# 11-_IMU.net
KiCad netlist of a schematic drawn in Altium Designer
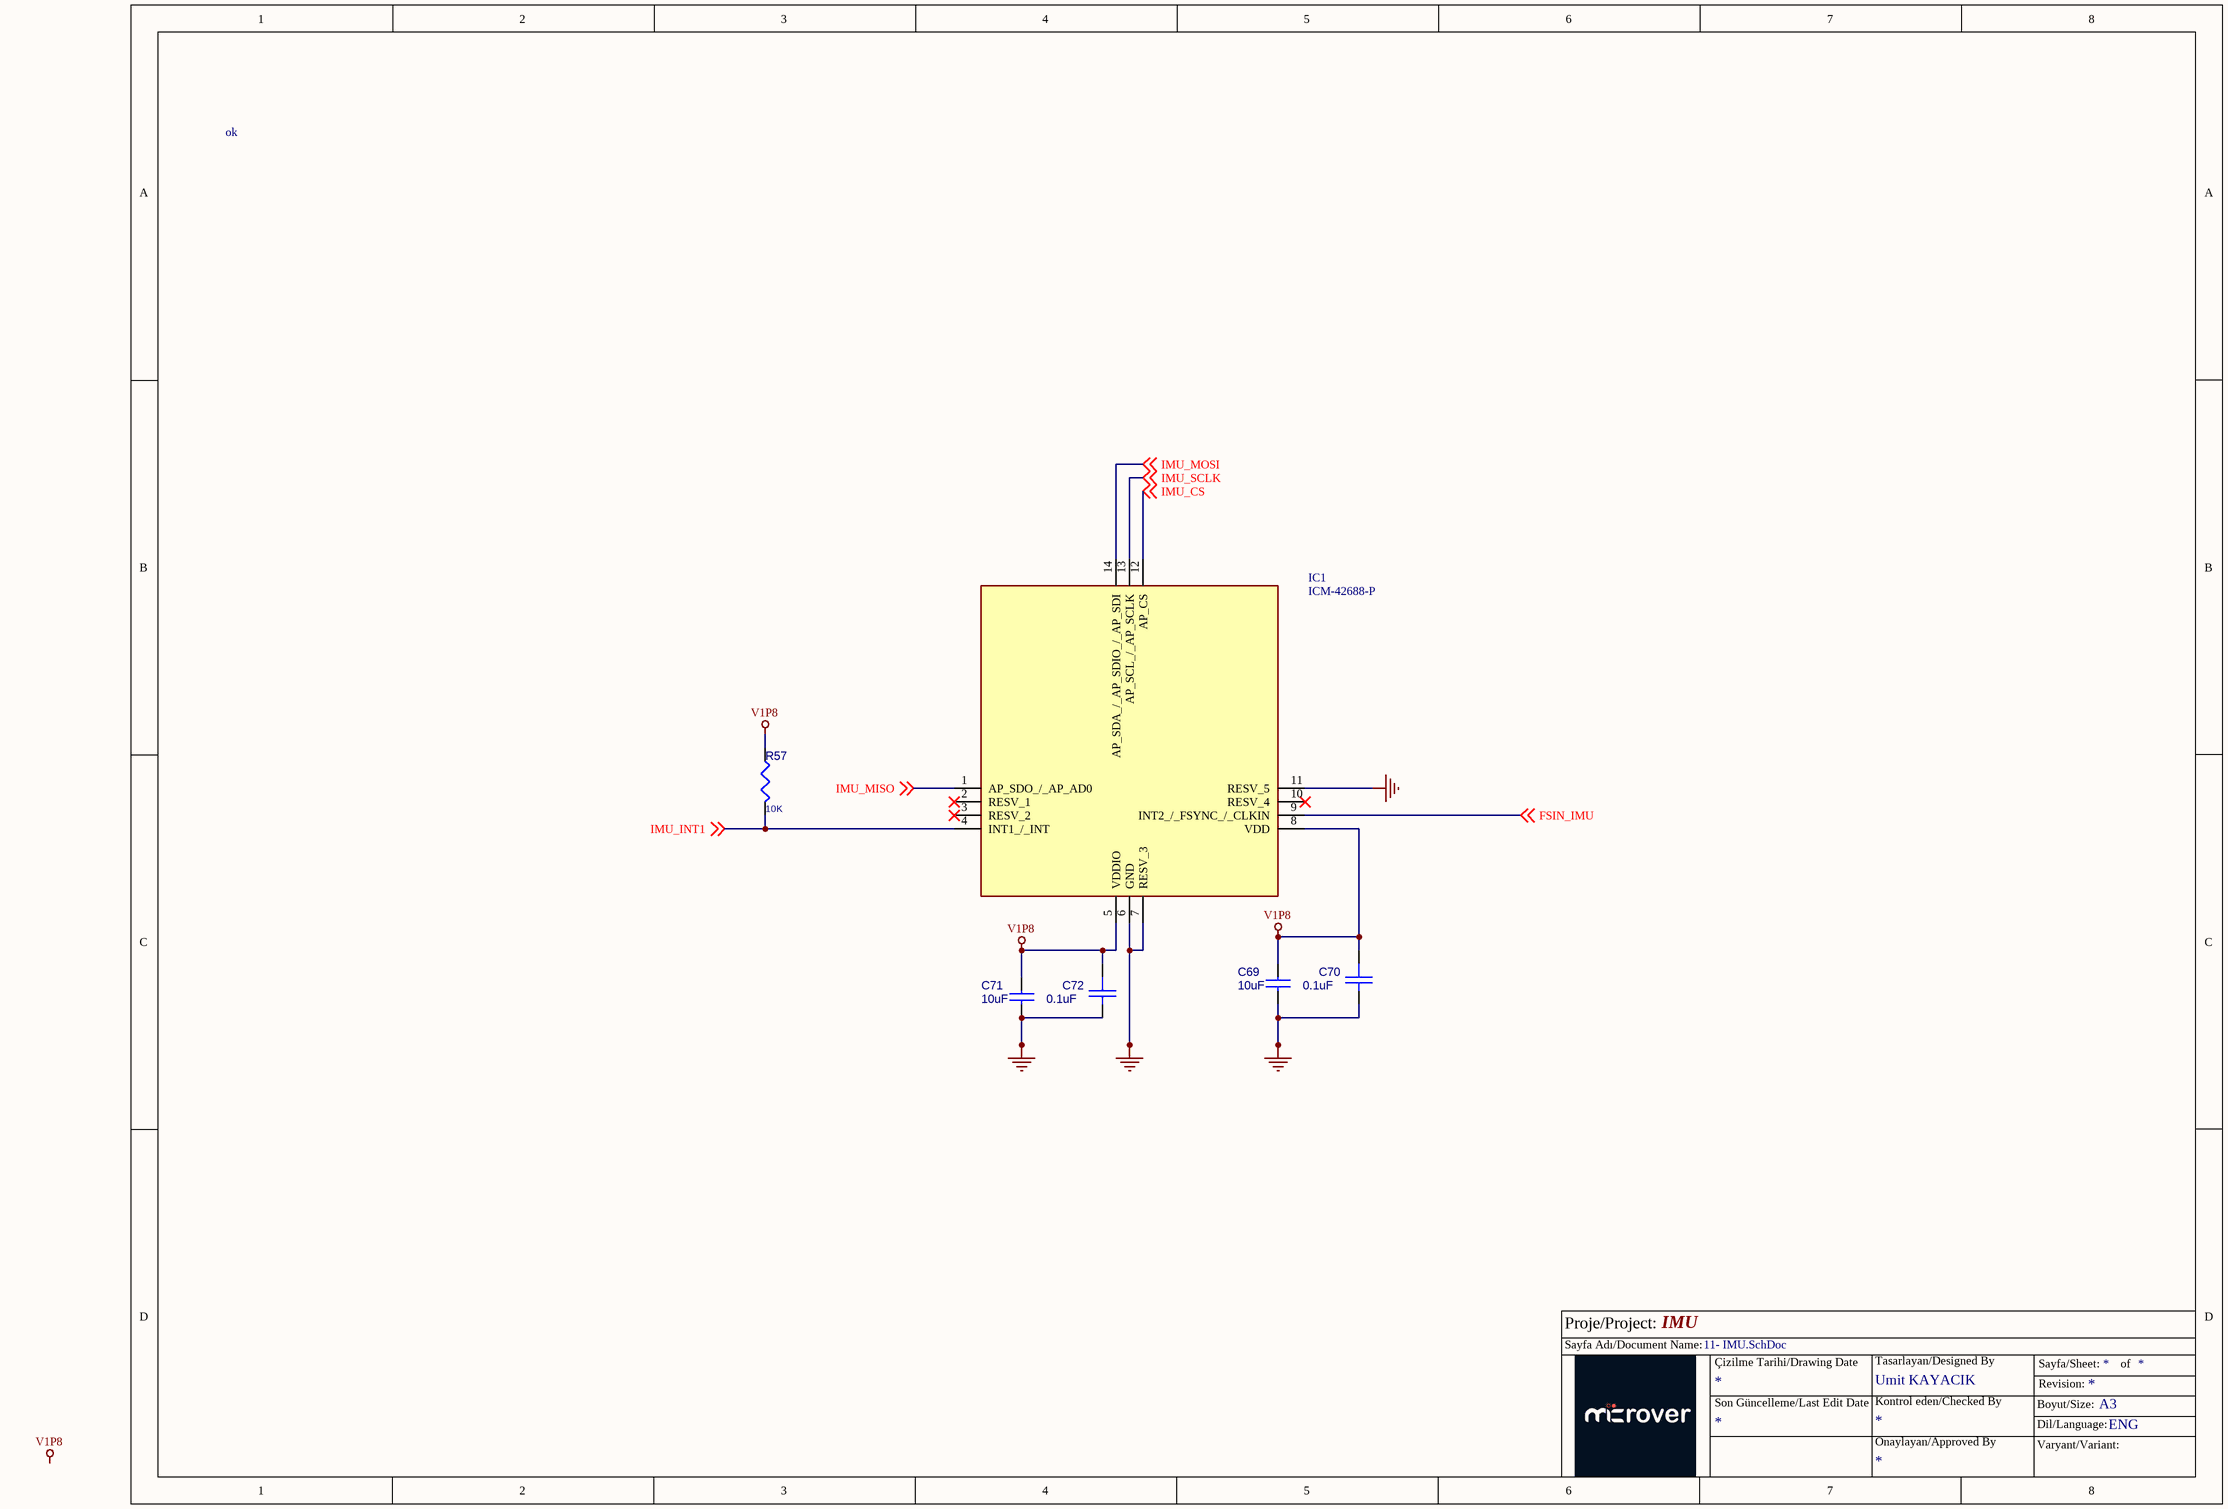
[diagram p0: 11- IMU.SchDoc]

(export (version "E")
  (design (tool "Eeschema 10.0.6"))
  (components
    (comp (ref "C69")
      (value "10uF")
      (footprint "C0603")
      (description "CAP CER 10UF 10V 20% X6S 0603")
      (fields (field (name "MFG") "Samsung") (field (name "MAN. PART #") "CL10X106MP8NRNC"))
      (libsource (lib "*") (part "CAP NP"))
    )
    (comp (ref "C70")
      (value "0.1uF")
      (footprint "C0201")
      (description "CAP CER 0.1UF 25V 10% X5R 0201")
      (fields
        (field (name "MANUFACTURER") "Murata")
        (field (name "MANUFACTURER PART NUMBER") "GRM033R61E104KE14J")
      )
      (libsource (lib "*") (part "CAP_SMT_0805"))
    )
    (comp (ref "C71")
      (value "10uF")
      (footprint "C0603")
      (description "CAP CER 10UF 10V 20% X6S 0603")
      (fields (field (name "MFG") "Samsung") (field (name "MAN. PART #") "CL10X106MP8NRNC"))
      (libsource (lib "*") (part "CAP NP"))
    )
    (comp (ref "C72")
      (value "0.1uF")
      (footprint "C0201")
      (description "CAP CER 0.1UF 25V 10% X5R 0201")
      (fields
        (field (name "MANUFACTURER") "Murata")
        (field (name "MANUFACTURER PART NUMBER") "GRM033R61E104KE14J")
      )
      (libsource (lib "*") (part "CAP_SMT_0805"))
    )
    (comp (ref "IC1")
      (value "ICM-42688-P")
      (footprint "IIM42352")
      (description "Integrated Circuit")
      (fields (field (name "MOUSER PART NUMBER") "410-ICM-42688-P"))
      (libsource (lib "Chronos") (part "ICM-42688-P"))
    )
    (comp (ref "R57")
      (value "10K")
      (footprint "R0402")
      (description "RES 10K OHM 1/10W 5% 0603")
      (fields
        (field (name "MFG") "Stackpole Electronics Inc")
        (field (name "MANUFACTURER PART NUMBER") "RMCF0603JT10K0")
      )
      (libsource (lib "*") (part "RES_10K_1W16_0402_5P"))
    )
  )
  (nets
    (net (code "1") (name "FSIN_IMU") (class "Default")
      (node (ref "IC1") (pin "9") (pinfunction "INT2_/_FSYNC_/_CLKIN_9") (pintype "passive"))
    )
    (net (code "2") (name "GND") (class "Default")
      (node (ref "C69") (pin "2") (pinfunction "2_2") (pintype "passive"))
      (node (ref "C70") (pin "2") (pinfunction "2_2") (pintype "passive"))
      (node (ref "C71") (pin "2") (pinfunction "2_2") (pintype "passive"))
      (node (ref "C72") (pin "2") (pinfunction "2_2") (pintype "passive"))
      (node (ref "IC1") (pin "11") (pinfunction "RESV_5_11") (pintype "passive"))
      (node (ref "IC1") (pin "6") (pinfunction "GND_6") (pintype "passive"))
      (node (ref "IC1") (pin "7") (pinfunction "RESV_3_7") (pintype "passive"))
    )
    (net (code "3") (name "IMU_CS") (class "Default")
      (node (ref "IC1") (pin "12") (pinfunction "AP_CS_12") (pintype "passive"))
    )
    (net (code "4") (name "IMU_INT1") (class "Default")
      (node (ref "IC1") (pin "4") (pinfunction "INT1_/_INT_4") (pintype "passive"))
      (node (ref "R57") (pin "2") (pinfunction "2_2") (pintype "passive"))
    )
    (net (code "5") (name "IMU_MISO") (class "Default")
      (node (ref "IC1") (pin "1") (pinfunction "AP_SDO_/_AP_AD0_1") (pintype "passive"))
    )
    (net (code "6") (name "IMU_MOSI") (class "Default")
      (node (ref "IC1") (pin "14") (pinfunction "AP_SDA_/_AP_SDIO_/_AP_SDI_14") (pintype "passive"))
    )
    (net (code "7") (name "IMU_SCLK") (class "Default")
      (node (ref "IC1") (pin "13") (pinfunction "AP_SCL_/_AP_SCLK_13") (pintype "passive"))
    )
    (net (code "8") (name "V1P8") (class "Default")
      (node (ref "C69") (pin "1") (pinfunction "1_1") (pintype "passive"))
      (node (ref "C70") (pin "1") (pinfunction "1_1") (pintype "passive"))
      (node (ref "C71") (pin "1") (pinfunction "1_1") (pintype "passive"))
      (node (ref "C72") (pin "1") (pinfunction "1_1") (pintype "passive"))
      (node (ref "IC1") (pin "5") (pinfunction "VDDIO_5") (pintype "passive"))
      (node (ref "IC1") (pin "8") (pinfunction "VDD_8") (pintype "passive"))
      (node (ref "R57") (pin "1") (pinfunction "1_1") (pintype "passive"))
    )
    (net (code "9") (name "unconnected-(IC1-RESV_1-Pad2)") (class "Default")
      (node (ref "IC1") (pin "2") (pinfunction "RESV_1_2") (pintype "passive+no_connect"))
    )
    (net (code "10") (name "unconnected-(IC1-RESV_2-Pad3)") (class "Default")
      (node (ref "IC1") (pin "3") (pinfunction "RESV_2_3") (pintype "passive+no_connect"))
    )
    (net (code "11") (name "unconnected-(IC1-RESV_4-Pad10)") (class "Default")
      (node (ref "IC1") (pin "10") (pinfunction "RESV_4_10") (pintype "passive+no_connect"))
    )
  )
)
